# PID_Schematic.net
KiCad netlist of a schematic drawn in Altium Designer
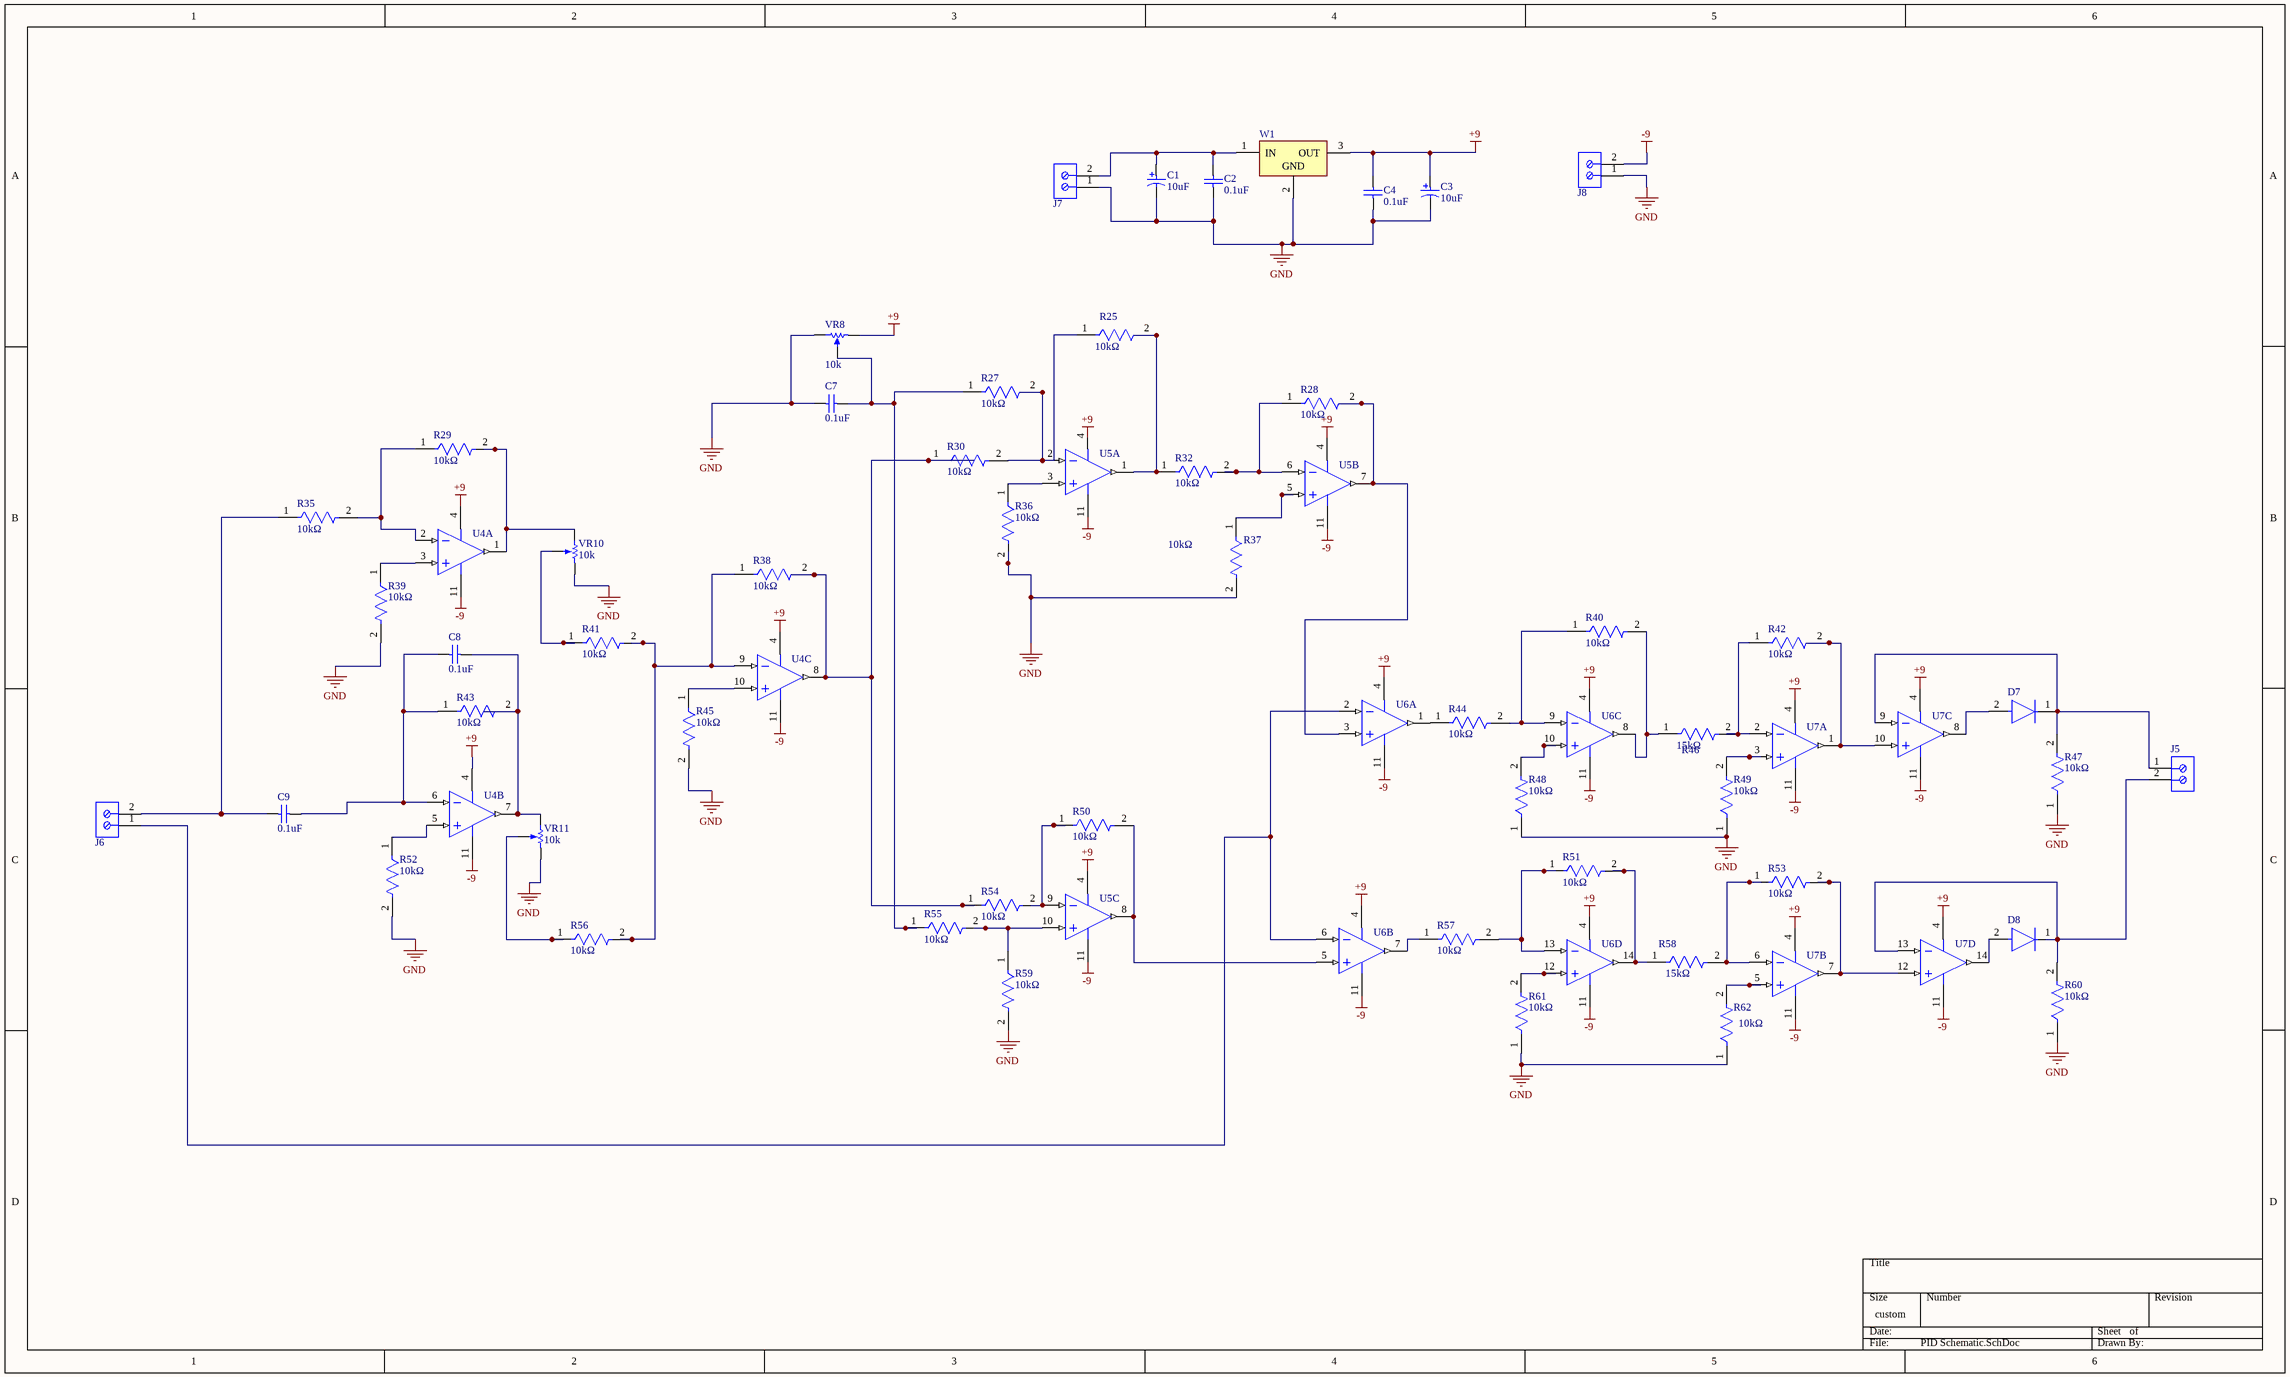
[diagram p0: PID Schematic.SchDoc]

(export (version "E")
  (design (tool "Eeschema 10.0.6"))
  (components
    (comp (ref "C1")
      (value "ECA1HM100")
      (footprint "CAPPR55-200-1100X500X1200")
      (description "Aluminum Electrolytic Capacitor, 10 uF, +/- 20%, 50 V, -40 to 85 degC, 2-Pin THD, RoHS, Bulk")
      (fields
        (field (name "MANUFACTURER") "Panasonic")
        (field (name "CAPACITANCE") "10uF")
        (field (name "TOLERANCE") "20%")
      )
      (libsource (lib "Altium Content Vault") (part "CAP-P-2"))
    )
    (comp (ref "C2")
      (value "0.1uF")
      (footprint "CAPR51-254-508X318X736")
      (fields (field (name "Comment") "C320C104K5R5TA"))
      (libsource (lib "Altium Content Vault") (part "CAP-NP-2"))
    )
    (comp (ref "C3")
      (value "ECA1HM100")
      (footprint "CAPPR55-200-1100X500X1200")
      (description "Aluminum Electrolytic Capacitor, 10 uF, +/- 20%, 50 V, -40 to 85 degC, 2-Pin THD, RoHS, Bulk")
      (fields
        (field (name "MANUFACTURER") "Panasonic")
        (field (name "CAPACITANCE") "10uF")
        (field (name "TOLERANCE") "20%")
      )
      (libsource (lib "Altium Content Vault") (part "CAP-P-2"))
    )
    (comp (ref "C4")
      (value "0.1uF")
      (footprint "CAPR51-254-508X318X736")
      (fields (field (name "Comment") "C320C104K5R5TA"))
      (libsource (lib "Altium Content Vault") (part "CAP-NP-2"))
    )
    (comp (ref "C7")
      (value "0.1uF")
      (footprint "CAPR51-254-508X318X736")
      (fields (field (name "Comment") "C320C104K5R5TA"))
      (libsource (lib "Altium Content Vault") (part "CAP-NP-2"))
    )
    (comp (ref "C8")
      (value "0.1uF")
      (footprint "CAPR51-254-508X318X736")
      (fields (field (name "Comment") "C320C104K5R5TA"))
      (libsource (lib "Altium Content Vault") (part "CAP-NP-2"))
    )
    (comp (ref "C9")
      (value "0.1uF")
      (footprint "CAPR51-254-508X318X736")
      (fields (field (name "Comment") "C320C104K5R5TA"))
      (libsource (lib "Altium Content Vault") (part "CAP-NP-2"))
    )
    (comp (ref "D7")
      (value "1N4148")
      (footprint "FP-017AG-MFG")
      (description "DIODE GEN PURP 100V 200MA DO35")
      (fields (field (name "VOLTAGE") "100V"))
      (libsource (lib "Altium Content Vault") (part "d7152d700b627762746794eb795d46e"))
    )
    (comp (ref "D8")
      (value "1N4148")
      (footprint "FP-017AG-MFG")
      (description "DIODE GEN PURP 100V 200MA DO35")
      (fields (field (name "VOLTAGE") "100V"))
      (libsource (lib "Altium Content Vault") (part "d7152d700b627762746794eb795d46e"))
    )
    (comp (ref "J5")
      (value "691103110002")
      (footprint "691103110002")
      (description "Series 1031 - 3.50 mm Horizontal Entry Modular with Pressure Clamp WR-TBL, 2 pin")
      (fields (field (name "MANUFACTURER") "Wurth Elektronik") (field (name "PUBLISHER") "WurthElektronik"))
      (libsource (lib "Altium Content Vault") (part "WE-CN-1P-F-TB2"))
    )
    (comp (ref "J6")
      (value "691103110002")
      (footprint "691103110002")
      (description "Series 1031 - 3.50 mm Horizontal Entry Modular with Pressure Clamp WR-TBL, 2 pin")
      (fields (field (name "MANUFACTURER") "Wurth Elektronik") (field (name "PUBLISHER") "WurthElektronik"))
      (libsource (lib "Altium Content Vault") (part "WE-CN-1P-F-TB2"))
    )
    (comp (ref "J7")
      (value "691103110002")
      (footprint "691103110002")
      (description "Series 1031 - 3.50 mm Horizontal Entry Modular with Pressure Clamp WR-TBL, 2 pin")
      (fields (field (name "MANUFACTURER") "Wurth Elektronik") (field (name "PUBLISHER") "WurthElektronik"))
      (libsource (lib "Altium Content Vault") (part "WE-CN-1P-F-TB2"))
    )
    (comp (ref "J8")
      (value "691103110002")
      (footprint "691103110002")
      (description "Series 1031 - 3.50 mm Horizontal Entry Modular with Pressure Clamp WR-TBL, 2 pin")
      (fields (field (name "MANUFACTURER") "Wurth Elektronik") (field (name "PUBLISHER") "WurthElektronik"))
      (libsource (lib "Altium Content Vault") (part "WE-CN-1P-F-TB2"))
    )
    (comp (ref "R25")
      (value "MRS25000C1101FCT00")
      (footprint "FP-MRS25-MFG")
      (description "RES 1.1K OHM 0.6W 1% AXIAL")
      (fields
        (field (name "MANUFACTURER") "Vishay BC Components")
        (field (name "OCTOPART") "https://octopart.com/mrs25000c1101fct00-vishay-43740214")
        (field (name "RESISTANCE") "10kΩ")
      )
      (libsource (lib "Altium Content Vault") (part "1029c3af85768c4190bb7ad29bc67b5"))
    )
    (comp (ref "R27")
      (value "MRS25000C1101FCT00")
      (footprint "FP-MRS25-MFG")
      (description "RES 1.1K OHM 0.6W 1% AXIAL")
      (fields
        (field (name "MANUFACTURER") "Vishay BC Components")
        (field (name "OCTOPART") "https://octopart.com/mrs25000c1101fct00-vishay-43740214")
        (field (name "RESISTANCE") "10kΩ")
      )
      (libsource (lib "Altium Content Vault") (part "1029c3af85768c4190bb7ad29bc67b5"))
    )
    (comp (ref "R28")
      (value "MRS25000C1101FCT00")
      (footprint "FP-MRS25-MFG")
      (description "RES 1.1K OHM 0.6W 1% AXIAL")
      (fields
        (field (name "MANUFACTURER") "Vishay BC Components")
        (field (name "OCTOPART") "https://octopart.com/mrs25000c1101fct00-vishay-43740214")
        (field (name "RESISTANCE") "10kΩ")
      )
      (libsource (lib "Altium Content Vault") (part "1029c3af85768c4190bb7ad29bc67b5"))
    )
    (comp (ref "R29")
      (value "MRS25000C1101FCT00")
      (footprint "FP-MRS25-MFG")
      (description "RES 1.1K OHM 0.6W 1% AXIAL")
      (fields
        (field (name "MANUFACTURER") "Vishay BC Components")
        (field (name "OCTOPART") "https://octopart.com/mrs25000c1101fct00-vishay-43740214")
        (field (name "RESISTANCE") "10kΩ")
      )
      (libsource (lib "Altium Content Vault") (part "1029c3af85768c4190bb7ad29bc67b5"))
    )
    (comp (ref "R30")
      (value "MRS25000C1101FCT00")
      (footprint "FP-MRS25-MFG")
      (description "RES 1.1K OHM 0.6W 1% AXIAL")
      (fields
        (field (name "MANUFACTURER") "Vishay BC Components")
        (field (name "OCTOPART") "https://octopart.com/mrs25000c1101fct00-vishay-43740214")
        (field (name "RESISTANCE") "10kΩ")
      )
      (libsource (lib "Altium Content Vault") (part "1029c3af85768c4190bb7ad29bc67b5"))
    )
    (comp (ref "R32")
      (value "MRS25000C1101FCT00")
      (footprint "FP-MRS25-MFG")
      (description "RES 1.1K OHM 0.6W 1% AXIAL")
      (fields
        (field (name "MANUFACTURER") "Vishay BC Components")
        (field (name "OCTOPART") "https://octopart.com/mrs25000c1101fct00-vishay-43740214")
        (field (name "RESISTANCE") "10kΩ")
      )
      (libsource (lib "Altium Content Vault") (part "1029c3af85768c4190bb7ad29bc67b5"))
    )
    (comp (ref "R35")
      (value "MRS25000C1101FCT00")
      (footprint "FP-MRS25-MFG")
      (description "RES 1.1K OHM 0.6W 1% AXIAL")
      (fields
        (field (name "MANUFACTURER") "Vishay BC Components")
        (field (name "OCTOPART") "https://octopart.com/mrs25000c1101fct00-vishay-43740214")
        (field (name "RESISTANCE") "10kΩ")
      )
      (libsource (lib "Altium Content Vault") (part "1029c3af85768c4190bb7ad29bc67b5"))
    )
    (comp (ref "R36")
      (value "MRS25000C1101FCT00")
      (footprint "FP-MRS25-MFG")
      (description "RES 1.1K OHM 0.6W 1% AXIAL")
      (fields
        (field (name "MANUFACTURER") "Vishay BC Components")
        (field (name "OCTOPART") "https://octopart.com/mrs25000c1101fct00-vishay-43740214")
        (field (name "RESISTANCE") "10kΩ")
      )
      (libsource (lib "Altium Content Vault") (part "1029c3af85768c4190bb7ad29bc67b5"))
    )
    (comp (ref "R37")
      (value "MRS25000C1101FCT00")
      (footprint "FP-MRS25-MFG")
      (description "RES 1.1K OHM 0.6W 1% AXIAL")
      (fields
        (field (name "MANUFACTURER") "Vishay BC Components")
        (field (name "OCTOPART") "https://octopart.com/mrs25000c1101fct00-vishay-43740214")
        (field (name "RESISTANCE") "10kΩ")
      )
      (libsource (lib "Altium Content Vault") (part "1029c3af85768c4190bb7ad29bc67b5"))
    )
    (comp (ref "R38")
      (value "MRS25000C1101FCT00")
      (footprint "FP-MRS25-MFG")
      (description "RES 1.1K OHM 0.6W 1% AXIAL")
      (fields
        (field (name "MANUFACTURER") "Vishay BC Components")
        (field (name "OCTOPART") "https://octopart.com/mrs25000c1101fct00-vishay-43740214")
        (field (name "RESISTANCE") "10kΩ")
      )
      (libsource (lib "Altium Content Vault") (part "1029c3af85768c4190bb7ad29bc67b5"))
    )
    (comp (ref "R39")
      (value "MRS25000C1101FCT00")
      (footprint "FP-MRS25-MFG")
      (description "RES 1.1K OHM 0.6W 1% AXIAL")
      (fields
        (field (name "MANUFACTURER") "Vishay BC Components")
        (field (name "OCTOPART") "https://octopart.com/mrs25000c1101fct00-vishay-43740214")
        (field (name "RESISTANCE") "10kΩ")
      )
      (libsource (lib "Altium Content Vault") (part "1029c3af85768c4190bb7ad29bc67b5"))
    )
    (comp (ref "R40")
      (value "MRS25000C1101FCT00")
      (footprint "FP-MRS25-MFG")
      (description "RES 1.1K OHM 0.6W 1% AXIAL")
      (fields
        (field (name "MANUFACTURER") "Vishay BC Components")
        (field (name "OCTOPART") "https://octopart.com/mrs25000c1101fct00-vishay-43740214")
        (field (name "RESISTANCE") "10kΩ")
      )
      (libsource (lib "Altium Content Vault") (part "1029c3af85768c4190bb7ad29bc67b5"))
    )
    (comp (ref "R41")
      (value "MRS25000C1101FCT00")
      (footprint "FP-MRS25-MFG")
      (description "RES 1.1K OHM 0.6W 1% AXIAL")
      (fields
        (field (name "MANUFACTURER") "Vishay BC Components")
        (field (name "OCTOPART") "https://octopart.com/mrs25000c1101fct00-vishay-43740214")
        (field (name "RESISTANCE") "10kΩ")
      )
      (libsource (lib "Altium Content Vault") (part "1029c3af85768c4190bb7ad29bc67b5"))
    )
    (comp (ref "R42")
      (value "MRS25000C1101FCT00")
      (footprint "FP-MRS25-MFG")
      (description "RES 1.1K OHM 0.6W 1% AXIAL")
      (fields
        (field (name "MANUFACTURER") "Vishay BC Components")
        (field (name "OCTOPART") "https://octopart.com/mrs25000c1101fct00-vishay-43740214")
        (field (name "RESISTANCE") "10kΩ")
      )
      (libsource (lib "Altium Content Vault") (part "1029c3af85768c4190bb7ad29bc67b5"))
    )
    (comp (ref "R43")
      (value "MRS25000C1101FCT00")
      (footprint "FP-MRS25-MFG")
      (description "RES 1.1K OHM 0.6W 1% AXIAL")
      (fields
        (field (name "MANUFACTURER") "Vishay BC Components")
        (field (name "OCTOPART") "https://octopart.com/mrs25000c1101fct00-vishay-43740214")
        (field (name "RESISTANCE") "10kΩ")
      )
      (libsource (lib "Altium Content Vault") (part "1029c3af85768c4190bb7ad29bc67b5"))
    )
    (comp (ref "R44")
      (value "MRS25000C1101FCT00")
      (footprint "FP-MRS25-MFG")
      (description "RES 1.1K OHM 0.6W 1% AXIAL")
      (fields
        (field (name "MANUFACTURER") "Vishay BC Components")
        (field (name "OCTOPART") "https://octopart.com/mrs25000c1101fct00-vishay-43740214")
        (field (name "RESISTANCE") "10kΩ")
      )
      (libsource (lib "Altium Content Vault") (part "1029c3af85768c4190bb7ad29bc67b5"))
    )
    (comp (ref "R45")
      (value "MRS25000C1101FCT00")
      (footprint "FP-MRS25-MFG")
      (description "RES 1.1K OHM 0.6W 1% AXIAL")
      (fields
        (field (name "MANUFACTURER") "Vishay BC Components")
        (field (name "OCTOPART") "https://octopart.com/mrs25000c1101fct00-vishay-43740214")
        (field (name "RESISTANCE") "10kΩ")
      )
      (libsource (lib "Altium Content Vault") (part "1029c3af85768c4190bb7ad29bc67b5"))
    )
    (comp (ref "R46")
      (value "MRS25000C1101FCT00")
      (footprint "FP-MRS25-MFG")
      (description "RES 1.1K OHM 0.6W 1% AXIAL")
      (fields
        (field (name "MANUFACTURER") "Vishay BC Components")
        (field (name "OCTOPART") "https://octopart.com/mrs25000c1101fct00-vishay-43740214")
        (field (name "RESISTANCE") "15kΩ")
      )
      (libsource (lib "Altium Content Vault") (part "1029c3af85768c4190bb7ad29bc67b5"))
    )
    (comp (ref "R47")
      (value "MRS25000C1101FCT00")
      (footprint "FP-MRS25-MFG")
      (description "RES 1.1K OHM 0.6W 1% AXIAL")
      (fields
        (field (name "MANUFACTURER") "Vishay BC Components")
        (field (name "OCTOPART") "https://octopart.com/mrs25000c1101fct00-vishay-43740214")
        (field (name "RESISTANCE") "10kΩ")
      )
      (libsource (lib "Altium Content Vault") (part "1029c3af85768c4190bb7ad29bc67b5"))
    )
    (comp (ref "R48")
      (value "MRS25000C1101FCT00")
      (footprint "FP-MRS25-MFG")
      (description "RES 1.1K OHM 0.6W 1% AXIAL")
      (fields
        (field (name "MANUFACTURER") "Vishay BC Components")
        (field (name "OCTOPART") "https://octopart.com/mrs25000c1101fct00-vishay-43740214")
        (field (name "RESISTANCE") "10kΩ")
      )
      (libsource (lib "Altium Content Vault") (part "1029c3af85768c4190bb7ad29bc67b5"))
    )
    (comp (ref "R49")
      (value "MRS25000C1101FCT00")
      (footprint "FP-MRS25-MFG")
      (description "RES 1.1K OHM 0.6W 1% AXIAL")
      (fields
        (field (name "MANUFACTURER") "Vishay BC Components")
        (field (name "OCTOPART") "https://octopart.com/mrs25000c1101fct00-vishay-43740214")
        (field (name "RESISTANCE") "10kΩ")
      )
      (libsource (lib "Altium Content Vault") (part "1029c3af85768c4190bb7ad29bc67b5"))
    )
    (comp (ref "R50")
      (value "MRS25000C1101FCT00")
      (footprint "FP-MRS25-MFG")
      (description "RES 1.1K OHM 0.6W 1% AXIAL")
      (fields
        (field (name "MANUFACTURER") "Vishay BC Components")
        (field (name "OCTOPART") "https://octopart.com/mrs25000c1101fct00-vishay-43740214")
        (field (name "RESISTANCE") "10kΩ")
      )
      (libsource (lib "Altium Content Vault") (part "1029c3af85768c4190bb7ad29bc67b5"))
    )
    (comp (ref "R51")
      (value "MRS25000C1101FCT00")
      (footprint "FP-MRS25-MFG")
      (description "RES 1.1K OHM 0.6W 1% AXIAL")
      (fields
        (field (name "MANUFACTURER") "Vishay BC Components")
        (field (name "OCTOPART") "https://octopart.com/mrs25000c1101fct00-vishay-43740214")
        (field (name "RESISTANCE") "10kΩ")
      )
      (libsource (lib "Altium Content Vault") (part "1029c3af85768c4190bb7ad29bc67b5"))
    )
    (comp (ref "R52")
      (value "MRS25000C1101FCT00")
      (footprint "FP-MRS25-MFG")
      (description "RES 1.1K OHM 0.6W 1% AXIAL")
      (fields
        (field (name "MANUFACTURER") "Vishay BC Components")
        (field (name "OCTOPART") "https://octopart.com/mrs25000c1101fct00-vishay-43740214")
        (field (name "RESISTANCE") "10kΩ")
      )
      (libsource (lib "Altium Content Vault") (part "1029c3af85768c4190bb7ad29bc67b5"))
    )
    (comp (ref "R53")
      (value "MRS25000C1101FCT00")
      (footprint "FP-MRS25-MFG")
      (description "RES 1.1K OHM 0.6W 1% AXIAL")
      (fields
        (field (name "MANUFACTURER") "Vishay BC Components")
        (field (name "OCTOPART") "https://octopart.com/mrs25000c1101fct00-vishay-43740214")
        (field (name "RESISTANCE") "10kΩ")
      )
      (libsource (lib "Altium Content Vault") (part "1029c3af85768c4190bb7ad29bc67b5"))
    )
    (comp (ref "R54")
      (value "MRS25000C1101FCT00")
      (footprint "FP-MRS25-MFG")
      (description "RES 1.1K OHM 0.6W 1% AXIAL")
      (fields
        (field (name "MANUFACTURER") "Vishay BC Components")
        (field (name "OCTOPART") "https://octopart.com/mrs25000c1101fct00-vishay-43740214")
        (field (name "RESISTANCE") "10kΩ")
      )
      (libsource (lib "Altium Content Vault") (part "1029c3af85768c4190bb7ad29bc67b5"))
    )
    (comp (ref "R55")
      (value "MRS25000C1101FCT00")
      (footprint "FP-MRS25-MFG")
      (description "RES 1.1K OHM 0.6W 1% AXIAL")
      (fields
        (field (name "MANUFACTURER") "Vishay BC Components")
        (field (name "OCTOPART") "https://octopart.com/mrs25000c1101fct00-vishay-43740214")
        (field (name "RESISTANCE") "10kΩ")
      )
      (libsource (lib "Altium Content Vault") (part "1029c3af85768c4190bb7ad29bc67b5"))
    )
    (comp (ref "R56")
      (value "MRS25000C1101FCT00")
      (footprint "FP-MRS25-MFG")
      (description "RES 1.1K OHM 0.6W 1% AXIAL")
      (fields
        (field (name "MANUFACTURER") "Vishay BC Components")
        (field (name "OCTOPART") "https://octopart.com/mrs25000c1101fct00-vishay-43740214")
        (field (name "RESISTANCE") "10kΩ")
      )
      (libsource (lib "Altium Content Vault") (part "1029c3af85768c4190bb7ad29bc67b5"))
    )
    (comp (ref "R57")
      (value "MRS25000C1101FCT00")
      (footprint "FP-MRS25-MFG")
      (description "RES 1.1K OHM 0.6W 1% AXIAL")
      (fields
        (field (name "MANUFACTURER") "Vishay BC Components")
        (field (name "OCTOPART") "https://octopart.com/mrs25000c1101fct00-vishay-43740214")
        (field (name "RESISTANCE") "10kΩ")
      )
      (libsource (lib "Altium Content Vault") (part "1029c3af85768c4190bb7ad29bc67b5"))
    )
    (comp (ref "R58")
      (value "MRS25000C1101FCT00")
      (footprint "FP-MRS25-MFG")
      (description "RES 1.1K OHM 0.6W 1% AXIAL")
      (fields
        (field (name "MANUFACTURER") "Vishay BC Components")
        (field (name "OCTOPART") "https://octopart.com/mrs25000c1101fct00-vishay-43740214")
        (field (name "RESISTANCE") "15kΩ")
      )
      (libsource (lib "Altium Content Vault") (part "1029c3af85768c4190bb7ad29bc67b5"))
    )
    (comp (ref "R59")
      (value "MRS25000C1101FCT00")
      (footprint "FP-MRS25-MFG")
      (description "RES 1.1K OHM 0.6W 1% AXIAL")
      (fields
        (field (name "MANUFACTURER") "Vishay BC Components")
        (field (name "OCTOPART") "https://octopart.com/mrs25000c1101fct00-vishay-43740214")
        (field (name "RESISTANCE") "10kΩ")
      )
      (libsource (lib "Altium Content Vault") (part "1029c3af85768c4190bb7ad29bc67b5"))
    )
    (comp (ref "R60")
      (value "MRS25000C1101FCT00")
      (footprint "FP-MRS25-MFG")
      (description "RES 1.1K OHM 0.6W 1% AXIAL")
      (fields
        (field (name "MANUFACTURER") "Vishay BC Components")
        (field (name "OCTOPART") "https://octopart.com/mrs25000c1101fct00-vishay-43740214")
        (field (name "RESISTANCE") "10kΩ")
      )
      (libsource (lib "Altium Content Vault") (part "1029c3af85768c4190bb7ad29bc67b5"))
    )
    (comp (ref "R61")
      (value "MRS25000C1101FCT00")
      (footprint "FP-MRS25-MFG")
      (description "RES 1.1K OHM 0.6W 1% AXIAL")
      (fields
        (field (name "MANUFACTURER") "Vishay BC Components")
        (field (name "OCTOPART") "https://octopart.com/mrs25000c1101fct00-vishay-43740214")
        (field (name "RESISTANCE") "10kΩ")
      )
      (libsource (lib "Altium Content Vault") (part "1029c3af85768c4190bb7ad29bc67b5"))
    )
    (comp (ref "R62")
      (value "MRS25000C1101FCT00")
      (footprint "FP-MRS25-MFG")
      (description "RES 1.1K OHM 0.6W 1% AXIAL")
      (fields
        (field (name "MANUFACTURER") "Vishay BC Components")
        (field (name "OCTOPART") "https://octopart.com/mrs25000c1101fct00-vishay-43740214")
        (field (name "RESISTANCE") "10kΩ")
      )
      (libsource (lib "Altium Content Vault") (part "1029c3af85768c4190bb7ad29bc67b5"))
    )
    (comp (ref "U4")
      (value "LM324N")
      (footprint "N0014A")
      (description "Low Power Quad Operational Amplifier, 14-pin MDIP")
      (fields (field (name "MANUFACTURER") "Texas Instruments"))
      (libsource (lib "Altium Content Vault") (part "AMP-OPA-LM124-14"))
    )
    (comp (ref "U5")
      (value "LM324N")
      (footprint "N0014A")
      (description "Low Power Quad Operational Amplifier, 14-pin MDIP")
      (fields (field (name "MANUFACTURER") "Texas Instruments"))
      (libsource (lib "Altium Content Vault") (part "AMP-OPA-LM124-14"))
    )
    (comp (ref "U6")
      (value "LM324N")
      (footprint "N0014A")
      (description "Low Power Quad Operational Amplifier, 14-pin MDIP")
      (fields (field (name "MANUFACTURER") "Texas Instruments"))
      (libsource (lib "Altium Content Vault") (part "AMP-OPA-LM124-14"))
    )
    (comp (ref "U7")
      (value "LM324N")
      (footprint "N0014A")
      (description "Low Power Quad Operational Amplifier, 14-pin MDIP")
      (fields (field (name "MANUFACTURER") "Texas Instruments"))
      (libsource (lib "Altium Content Vault") (part "AMP-OPA-LM124-14"))
    )
    (comp (ref "VR8")
      (value "3296W-1-103LF")
      (footprint "BOUR-3296W")
      (fields (field (name "RESISTANCE") "10k") (field (name "TOLERANCE") "1%"))
      (libsource (lib "Altium Content Vault") (part "RES-POT-3"))
    )
    (comp (ref "VR10")
      (value "3296W-1-103LF")
      (footprint "BOUR-3296W")
      (fields (field (name "RESISTANCE") "10k") (field (name "TOLERANCE") "1%"))
      (libsource (lib "Altium Content Vault") (part "RES-POT-3"))
    )
    (comp (ref "VR11")
      (value "3296W-1-103LF")
      (footprint "BOUR-3296W")
      (fields (field (name "RESISTANCE") "10k") (field (name "TOLERANCE") "1%"))
      (libsource (lib "Altium Content Vault") (part "RES-POT-3"))
    )
    (comp (ref "W1")
      (value "L7809CV")
      (footprint "TO220")
      (description "Positive Voltage Regulator, 9V, 3-Pin TO-220")
      (libsource (lib "Altium Content Vault") (part "PM-REG-L4940-SIL3"))
    )
  )
  (nets
    (net (code "1") (name "+9") (class "Default")
      (node (ref "C3") (pin "1") (pinfunction "1_1") (pintype "passive"))
      (node (ref "C4") (pin "1") (pinfunction "1_1") (pintype "passive"))
      (node (ref "U4") (pin "4") (pinfunction "V+_4") (pintype "power_in"))
      (node (ref "U5") (pin "4") (pinfunction "V+_4") (pintype "power_in"))
      (node (ref "U6") (pin "4") (pinfunction "V+_4") (pintype "power_in"))
      (node (ref "U7") (pin "4") (pinfunction "V+_4") (pintype "power_in"))
      (node (ref "VR8") (pin "3") (pinfunction "CW_3") (pintype "passive"))
      (node (ref "W1") (pin "3") (pinfunction "OUT_3") (pintype "power_in"))
    )
    (net (code "2") (name "-9") (class "Default")
      (node (ref "J8") (pin "2") (pinfunction "2_2") (pintype "passive"))
      (node (ref "U4") (pin "11") (pinfunction "GND_11") (pintype "power_in"))
      (node (ref "U5") (pin "11") (pinfunction "GND_11") (pintype "power_in"))
      (node (ref "U6") (pin "11") (pinfunction "GND_11") (pintype "power_in"))
      (node (ref "U7") (pin "11") (pinfunction "GND_11") (pintype "power_in"))
    )
    (net (code "3") (name "GND") (class "Default")
      (node (ref "C1") (pin "2") (pinfunction "2_2") (pintype "passive"))
      (node (ref "C2") (pin "2") (pinfunction "2_2") (pintype "passive"))
      (node (ref "C3") (pin "2") (pinfunction "2_2") (pintype "passive"))
      (node (ref "C4") (pin "2") (pinfunction "2_2") (pintype "passive"))
      (node (ref "C7") (pin "1") (pinfunction "1_1") (pintype "passive"))
      (node (ref "J7") (pin "1") (pinfunction "1_1") (pintype "passive"))
      (node (ref "J8") (pin "1") (pinfunction "1_1") (pintype "passive"))
      (node (ref "R36") (pin "2") (pinfunction "2_2") (pintype "passive"))
      (node (ref "R37") (pin "2") (pinfunction "2_2") (pintype "passive"))
      (node (ref "R39") (pin "2") (pinfunction "2_2") (pintype "passive"))
      (node (ref "R45") (pin "2") (pinfunction "2_2") (pintype "passive"))
      (node (ref "R47") (pin "1") (pinfunction "1_1") (pintype "passive"))
      (node (ref "R48") (pin "1") (pinfunction "1_1") (pintype "passive"))
      (node (ref "R49") (pin "1") (pinfunction "1_1") (pintype "passive"))
      (node (ref "R52") (pin "2") (pinfunction "2_2") (pintype "passive"))
      (node (ref "R59") (pin "2") (pinfunction "2_2") (pintype "passive"))
      (node (ref "R60") (pin "1") (pinfunction "1_1") (pintype "passive"))
      (node (ref "R61") (pin "1") (pinfunction "1_1") (pintype "passive"))
      (node (ref "R62") (pin "1") (pinfunction "1_1") (pintype "passive"))
      (node (ref "VR10") (pin "3") (pinfunction "CW_3") (pintype "passive"))
      (node (ref "VR11") (pin "3") (pinfunction "CW_3") (pintype "passive"))
      (node (ref "VR8") (pin "1") (pinfunction "CCW_1") (pintype "passive"))
      (node (ref "W1") (pin "2") (pinfunction "GND_2") (pintype "power_in"))
    )
    (net (code "4") (name "Net-(C9-Pad1)") (class "Default")
      (node (ref "C9") (pin "1") (pinfunction "1_1") (pintype "passive"))
      (node (ref "J6") (pin "2") (pinfunction "2_2") (pintype "passive"))
      (node (ref "R35") (pin "1") (pinfunction "1_1") (pintype "passive"))
    )
    (net (code "5") (name "Net-(D7-A)") (class "Default")
      (node (ref "D7") (pin "2") (pinfunction "A_2") (pintype "passive"))
      (node (ref "U7") (pin "8") (pinfunction "OUT3_8") (pintype "output"))
    )
    (net (code "6") (name "Net-(D7-C)") (class "Default")
      (node (ref "D7") (pin "1") (pinfunction "C_1") (pintype "passive"))
      (node (ref "J5") (pin "1") (pinfunction "1_1") (pintype "passive"))
      (node (ref "R47") (pin "2") (pinfunction "2_2") (pintype "passive"))
      (node (ref "U7") (pin "9") (pinfunction "IN3-_9") (pintype "input"))
    )
    (net (code "7") (name "Net-(D8-A)") (class "Default")
      (node (ref "D8") (pin "2") (pinfunction "A_2") (pintype "passive"))
      (node (ref "U7") (pin "14") (pinfunction "OUT4_14") (pintype "output"))
    )
    (net (code "8") (name "Net-(D8-C)") (class "Default")
      (node (ref "D8") (pin "1") (pinfunction "C_1") (pintype "passive"))
      (node (ref "J5") (pin "2") (pinfunction "2_2") (pintype "passive"))
      (node (ref "R60") (pin "2") (pinfunction "2_2") (pintype "passive"))
      (node (ref "U7") (pin "13") (pinfunction "IN4-_13") (pintype "input"))
    )
    (net (code "9") (name "Net-(U4A-IN1+)") (class "Default")
      (node (ref "R39") (pin "1") (pinfunction "1_1") (pintype "passive"))
      (node (ref "U4") (pin "3") (pinfunction "IN1+_3") (pintype "input"))
    )
    (net (code "10") (name "Net-(U4A-IN1-)") (class "Default")
      (node (ref "R29") (pin "1") (pinfunction "1_1") (pintype "passive"))
      (node (ref "R35") (pin "2") (pinfunction "2_2") (pintype "passive"))
      (node (ref "U4") (pin "2") (pinfunction "IN1-_2") (pintype "input"))
    )
    (net (code "11") (name "Net-(U4A-OUT1)") (class "Default")
      (node (ref "R29") (pin "2") (pinfunction "2_2") (pintype "passive"))
      (node (ref "U4") (pin "1") (pinfunction "OUT1_1") (pintype "output"))
      (node (ref "VR10") (pin "1") (pinfunction "CCW_1") (pintype "passive"))
    )
    (net (code "12") (name "Net-(U4B-IN2+)") (class "Default")
      (node (ref "R52") (pin "1") (pinfunction "1_1") (pintype "passive"))
      (node (ref "U4") (pin "5") (pinfunction "IN2+_5") (pintype "input"))
    )
    (net (code "13") (name "Net-(U4B-IN2-)") (class "Default")
      (node (ref "C8") (pin "1") (pinfunction "1_1") (pintype "passive"))
      (node (ref "C9") (pin "2") (pinfunction "2_2") (pintype "passive"))
      (node (ref "R43") (pin "1") (pinfunction "1_1") (pintype "passive"))
      (node (ref "U4") (pin "6") (pinfunction "IN2-_6") (pintype "input"))
    )
    (net (code "14") (name "Net-(U4B-OUT2)") (class "Default")
      (node (ref "C8") (pin "2") (pinfunction "2_2") (pintype "passive"))
      (node (ref "R43") (pin "2") (pinfunction "2_2") (pintype "passive"))
      (node (ref "U4") (pin "7") (pinfunction "OUT2_7") (pintype "output"))
      (node (ref "VR11") (pin "1") (pinfunction "CCW_1") (pintype "passive"))
    )
    (net (code "15") (name "Net-(U4C-IN3+)") (class "Default")
      (node (ref "R45") (pin "1") (pinfunction "1_1") (pintype "passive"))
      (node (ref "U4") (pin "10") (pinfunction "IN3+_10") (pintype "input"))
    )
    (net (code "16") (name "Net-(U4C-IN3-)") (class "Default")
      (node (ref "R38") (pin "1") (pinfunction "1_1") (pintype "passive"))
      (node (ref "R41") (pin "2") (pinfunction "2_2") (pintype "passive"))
      (node (ref "R56") (pin "2") (pinfunction "2_2") (pintype "passive"))
      (node (ref "U4") (pin "9") (pinfunction "IN3-_9") (pintype "input"))
    )
    (net (code "17") (name "Net-(U4C-OUT3)") (class "Default")
      (node (ref "R30") (pin "1") (pinfunction "1_1") (pintype "passive"))
      (node (ref "R38") (pin "2") (pinfunction "2_2") (pintype "passive"))
      (node (ref "R54") (pin "1") (pinfunction "1_1") (pintype "passive"))
      (node (ref "U4") (pin "8") (pinfunction "OUT3_8") (pintype "output"))
    )
    (net (code "18") (name "Net-(U5A-IN1+)") (class "Default")
      (node (ref "R36") (pin "1") (pinfunction "1_1") (pintype "passive"))
      (node (ref "U5") (pin "3") (pinfunction "IN1+_3") (pintype "input"))
    )
    (net (code "19") (name "Net-(U5A-IN1-)") (class "Default")
      (node (ref "R25") (pin "1") (pinfunction "1_1") (pintype "passive"))
      (node (ref "R27") (pin "2") (pinfunction "2_2") (pintype "passive"))
      (node (ref "R30") (pin "2") (pinfunction "2_2") (pintype "passive"))
      (node (ref "U5") (pin "2") (pinfunction "IN1-_2") (pintype "input"))
    )
    (net (code "20") (name "Net-(U5A-OUT1)") (class "Default")
      (node (ref "R25") (pin "2") (pinfunction "2_2") (pintype "passive"))
      (node (ref "R32") (pin "1") (pinfunction "1_1") (pintype "passive"))
      (node (ref "U5") (pin "1") (pinfunction "OUT1_1") (pintype "output"))
    )
    (net (code "21") (name "Net-(U5B-IN2+)") (class "Default")
      (node (ref "R37") (pin "1") (pinfunction "1_1") (pintype "passive"))
      (node (ref "U5") (pin "5") (pinfunction "IN2+_5") (pintype "input"))
    )
    (net (code "22") (name "Net-(U5B-IN2-)") (class "Default")
      (node (ref "R28") (pin "1") (pinfunction "1_1") (pintype "passive"))
      (node (ref "R32") (pin "2") (pinfunction "2_2") (pintype "passive"))
      (node (ref "U5") (pin "6") (pinfunction "IN2-_6") (pintype "input"))
    )
    (net (code "23") (name "Net-(U5B-OUT2)") (class "Default")
      (node (ref "R28") (pin "2") (pinfunction "2_2") (pintype "passive"))
      (node (ref "U5") (pin "7") (pinfunction "OUT2_7") (pintype "output"))
      (node (ref "U6") (pin "3") (pinfunction "IN1+_3") (pintype "input"))
    )
    (net (code "24") (name "Net-(U5C-IN3+)") (class "Default")
      (node (ref "R55") (pin "2") (pinfunction "2_2") (pintype "passive"))
      (node (ref "R59") (pin "1") (pinfunction "1_1") (pintype "passive"))
      (node (ref "U5") (pin "10") (pinfunction "IN3+_10") (pintype "input"))
    )
    (net (code "25") (name "Net-(U5C-IN3-)") (class "Default")
      (node (ref "R50") (pin "1") (pinfunction "1_1") (pintype "passive"))
      (node (ref "R54") (pin "2") (pinfunction "2_2") (pintype "passive"))
      (node (ref "U5") (pin "9") (pinfunction "IN3-_9") (pintype "input"))
    )
    (net (code "26") (name "Net-(U5C-OUT3)") (class "Default")
      (node (ref "R50") (pin "2") (pinfunction "2_2") (pintype "passive"))
      (node (ref "U5") (pin "8") (pinfunction "OUT3_8") (pintype "output"))
      (node (ref "U6") (pin "5") (pinfunction "IN2+_5") (pintype "input"))
    )
    (net (code "27") (name "Net-(U6A-IN1-)") (class "Default")
      (node (ref "J6") (pin "1") (pinfunction "1_1") (pintype "passive"))
      (node (ref "U6") (pin "2") (pinfunction "IN1-_2") (pintype "input"))
      (node (ref "U6") (pin "6") (pinfunction "IN2-_6") (pintype "input"))
    )
    (net (code "28") (name "Net-(U6A-OUT1)") (class "Default")
      (node (ref "R44") (pin "1") (pinfunction "1_1") (pintype "passive"))
      (node (ref "U6") (pin "1") (pinfunction "OUT1_1") (pintype "output"))
    )
    (net (code "29") (name "Net-(U6B-OUT2)") (class "Default")
      (node (ref "R57") (pin "1") (pinfunction "1_1") (pintype "passive"))
      (node (ref "U6") (pin "7") (pinfunction "OUT2_7") (pintype "output"))
    )
    (net (code "30") (name "Net-(U6C-IN3+)") (class "Default")
      (node (ref "R48") (pin "2") (pinfunction "2_2") (pintype "passive"))
      (node (ref "U6") (pin "10") (pinfunction "IN3+_10") (pintype "input"))
    )
    (net (code "31") (name "Net-(U6C-IN3-)") (class "Default")
      (node (ref "R40") (pin "1") (pinfunction "1_1") (pintype "passive"))
      (node (ref "R44") (pin "2") (pinfunction "2_2") (pintype "passive"))
      (node (ref "U6") (pin "9") (pinfunction "IN3-_9") (pintype "input"))
    )
    (net (code "32") (name "Net-(U6C-OUT3)") (class "Default")
      (node (ref "R40") (pin "2") (pinfunction "2_2") (pintype "passive"))
      (node (ref "R46") (pin "1") (pinfunction "1_1") (pintype "passive"))
      (node (ref "U6") (pin "8") (pinfunction "OUT3_8") (pintype "output"))
    )
    (net (code "33") (name "Net-(U6D-IN4+)") (class "Default")
      (node (ref "R61") (pin "2") (pinfunction "2_2") (pintype "passive"))
      (node (ref "U6") (pin "12") (pinfunction "IN4+_12") (pintype "input"))
    )
    (net (code "34") (name "Net-(U6D-IN4-)") (class "Default")
      (node (ref "R51") (pin "1") (pinfunction "1_1") (pintype "passive"))
      (node (ref "R57") (pin "2") (pinfunction "2_2") (pintype "passive"))
      (node (ref "U6") (pin "13") (pinfunction "IN4-_13") (pintype "input"))
    )
    (net (code "35") (name "Net-(U6D-OUT4)") (class "Default")
      (node (ref "R51") (pin "2") (pinfunction "2_2") (pintype "passive"))
      (node (ref "R58") (pin "1") (pinfunction "1_1") (pintype "passive"))
      (node (ref "U6") (pin "14") (pinfunction "OUT4_14") (pintype "output"))
    )
    (net (code "36") (name "Net-(U7A-IN1+)") (class "Default")
      (node (ref "R49") (pin "2") (pinfunction "2_2") (pintype "passive"))
      (node (ref "U7") (pin "3") (pinfunction "IN1+_3") (pintype "input"))
    )
    (net (code "37") (name "Net-(U7A-IN1-)") (class "Default")
      (node (ref "R42") (pin "1") (pinfunction "1_1") (pintype "passive"))
      (node (ref "R46") (pin "2") (pinfunction "2_2") (pintype "passive"))
      (node (ref "U7") (pin "2") (pinfunction "IN1-_2") (pintype "input"))
    )
    (net (code "38") (name "Net-(U7A-OUT1)") (class "Default")
      (node (ref "R42") (pin "2") (pinfunction "2_2") (pintype "passive"))
      (node (ref "U7") (pin "1") (pinfunction "OUT1_1") (pintype "output"))
      (node (ref "U7") (pin "10") (pinfunction "IN3+_10") (pintype "input"))
    )
    (net (code "39") (name "Net-(U7B-IN2+)") (class "Default")
      (node (ref "R62") (pin "2") (pinfunction "2_2") (pintype "passive"))
      (node (ref "U7") (pin "5") (pinfunction "IN2+_5") (pintype "input"))
    )
    (net (code "40") (name "Net-(U7B-IN2-)") (class "Default")
      (node (ref "R53") (pin "1") (pinfunction "1_1") (pintype "passive"))
      (node (ref "R58") (pin "2") (pinfunction "2_2") (pintype "passive"))
      (node (ref "U7") (pin "6") (pinfunction "IN2-_6") (pintype "input"))
    )
    (net (code "41") (name "Net-(U7B-OUT2)") (class "Default")
      (node (ref "R53") (pin "2") (pinfunction "2_2") (pintype "passive"))
      (node (ref "U7") (pin "12") (pinfunction "IN4+_12") (pintype "input"))
      (node (ref "U7") (pin "7") (pinfunction "OUT2_7") (pintype "output"))
    )
    (net (code "42") (name "Net-(VR8-S)") (class "Default")
      (node (ref "C7") (pin "2") (pinfunction "2_2") (pintype "passive"))
      (node (ref "R27") (pin "1") (pinfunction "1_1") (pintype "passive"))
      (node (ref "R55") (pin "1") (pinfunction "1_1") (pintype "passive"))
      (node (ref "VR8") (pin "2") (pinfunction "S_2") (pintype "passive"))
    )
    (net (code "43") (name "Net-(VR10-S)") (class "Default")
      (node (ref "R41") (pin "1") (pinfunction "1_1") (pintype "passive"))
      (node (ref "VR10") (pin "2") (pinfunction "S_2") (pintype "passive"))
    )
    (net (code "44") (name "Net-(VR11-S)") (class "Default")
      (node (ref "R56") (pin "1") (pinfunction "1_1") (pintype "passive"))
      (node (ref "VR11") (pin "2") (pinfunction "S_2") (pintype "passive"))
    )
    (net (code "45") (name "Net-(W1-IN)") (class "Default")
      (node (ref "C1") (pin "1") (pinfunction "1_1") (pintype "passive"))
      (node (ref "C2") (pin "1") (pinfunction "1_1") (pintype "passive"))
      (node (ref "J7") (pin "2") (pinfunction "2_2") (pintype "passive"))
      (node (ref "W1") (pin "1") (pinfunction "IN_1") (pintype "power_in"))
    )
    (net (code "46") (name "unconnected-(U5A-V+-Pad4)") (class "Default")
      (node (ref "U5") (pin "4") (pinfunction "V+_4") (pintype "power_in"))
    )
  )
)
